# RFM69_USB_Gateway_0_93.net
KiCad netlist of a schematic drawn in EAGLE
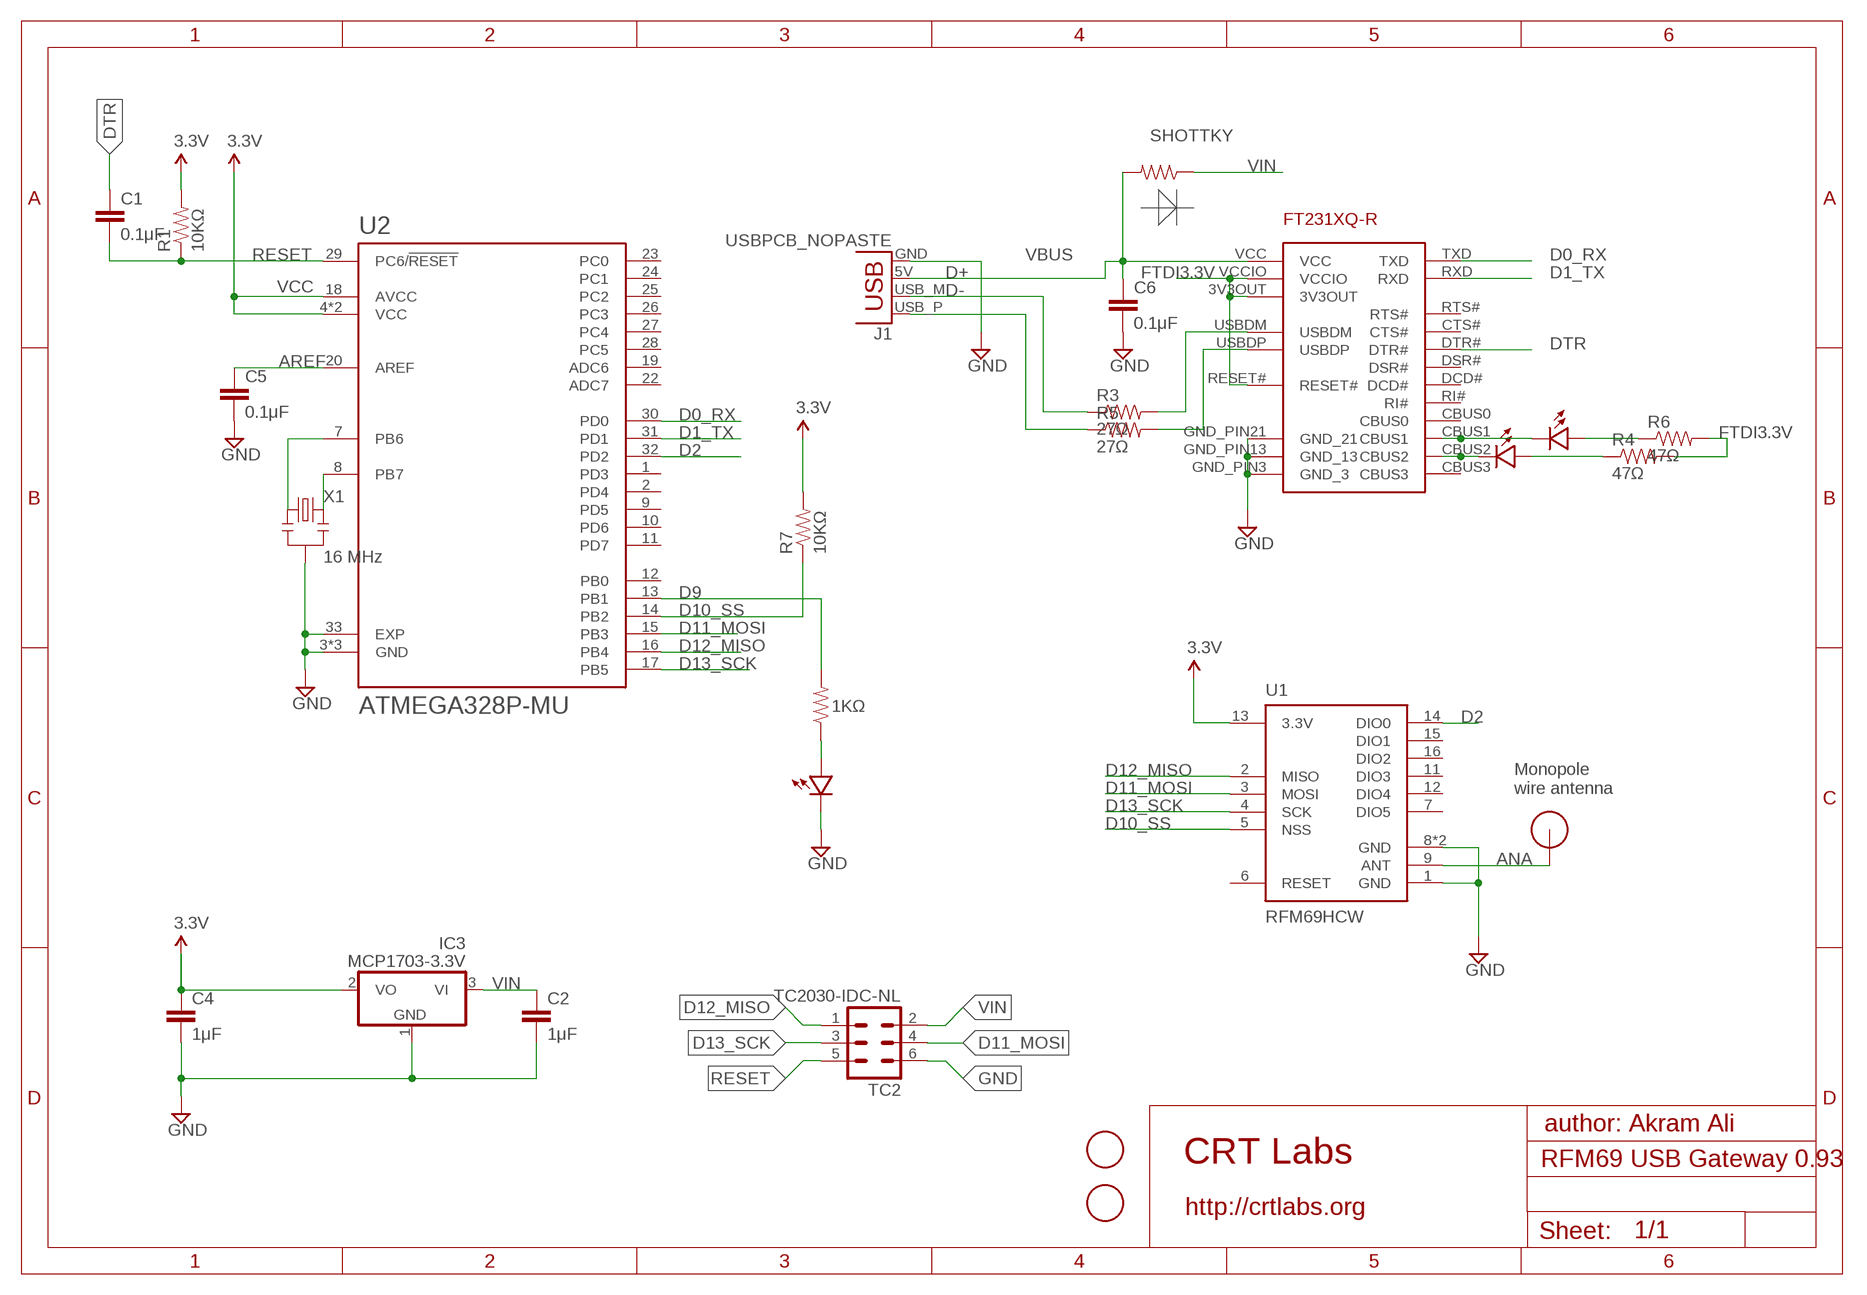
[diagram p0: schematic, sheet 1]

(export (version "E")
  (design (tool "Eeschema 10.0.6"))
  (components
    (comp (ref "C1")
      (value "0.1μF")
      (footprint "eagle-import:0805")
      (fields (field (name "MPN") "CC0805KRX7R9BB104"))
      (libsource (lib "eagle-import") (part "SparkFun_CAP0805"))
    )
    (comp (ref "C2")
      (value "1μF")
      (footprint "eagle-import:0805")
      (fields (field (name "MPN") "CC0805ZRY5V8BB105"))
      (libsource (lib "eagle-import") (part "SparkFun_CAP0805"))
    )
    (comp (ref "C4")
      (value "1μF")
      (footprint "eagle-import:0805")
      (fields (field (name "MPN") "CC0805ZRY5V8BB105"))
      (libsource (lib "eagle-import") (part "CAP0805"))
    )
    (comp (ref "C5")
      (value "0.1μF")
      (footprint "eagle-import:0805")
      (fields (field (name "MPN") "CC0805KRX7R9BB104"))
      (libsource (lib "eagle-import") (part "SparkFun_CAP0805"))
    )
    (comp (ref "C6")
      (value "0.1μF")
      (footprint "eagle-import:0805")
      (fields (field (name "MPN") "CC0805KRX7R9BB104"))
      (libsource (lib "eagle-import") (part "SparkFun_CAP0805"))
    )
    (comp (ref "D")
      (value "SHOTTKY")
      (footprint "eagle-import:0805")
      (fields (field (name "MPN") "SD0805S040S0R5"))
      (libsource (lib "eagle-import") (part "RESISTOR0805"))
    )
    (comp (ref "FT231XQ-R")
      (value "FT231XQ-R")
      (footprint "eagle-import:FTDI_FT231XQ-R_PACKAGE")
      (libsource (lib "eagle-import") (part "FT231XQ-R"))
    )
    (comp (ref "IC3")
      (value "MCP1703-3.3V")
      (footprint "eagle-import:SOT23")
      (fields (field (name "MPN") "MCP1703T-2502E/CB"))
      (libsource (lib "eagle-import") (part "MCP1703CB"))
    )
    (comp (ref "J1")
      (value "USBPCB_NOPASTE")
      (footprint "eagle-import:USB-A-PCB-NOPASTE")
      (libsource (lib "eagle-import") (part "USBPCB_NOPASTE"))
    )
    (comp (ref "R1")
      (value "10KΩ")
      (footprint "eagle-import:0805")
      (fields (field (name "MPN") "RC0805FR-0710KL"))
      (libsource (lib "eagle-import") (part "RESISTOR0805"))
    )
    (comp (ref "R2")
      (value "1KΩ")
      (footprint "eagle-import:0805")
      (fields (field (name "MPN") "RC0805FR-071KL"))
      (libsource (lib "eagle-import") (part "SparkFun_RESISTOR0805-RES"))
    )
    (comp (ref "R3")
      (value "27Ω")
      (footprint "eagle-import:0805")
      (fields (field (name "MPN") "RC0805FR-0727RL"))
      (libsource (lib "eagle-import") (part "SparkFun_RESISTOR0805-RES"))
    )
    (comp (ref "R4")
      (value "47Ω")
      (footprint "eagle-import:0805")
      (fields (field (name "MPN") "RC0805FR-0747RL "))
      (libsource (lib "eagle-import") (part "SparkFun_RESISTOR0805-RES"))
    )
    (comp (ref "R5")
      (value "27Ω")
      (footprint "eagle-import:0805")
      (fields (field (name "MPN") "RC0805FR-0727RL"))
      (libsource (lib "eagle-import") (part "SparkFun_RESISTOR0805-RES"))
    )
    (comp (ref "R6")
      (value "47Ω")
      (footprint "eagle-import:0805")
      (fields (field (name "MPN") "RC0805FR-0747RL "))
      (libsource (lib "eagle-import") (part "SparkFun_RESISTOR0805-RES"))
    )
    (comp (ref "R7")
      (value "10KΩ")
      (footprint "eagle-import:0805")
      (fields (field (name "MPN") "RC0805FR-0710KL"))
      (libsource (lib "eagle-import") (part "SparkFun_RESISTOR0805-RES"))
    )
    (comp (ref "RX")
      (value "Green")
      (footprint "eagle-import:0805-LED")
      (fields (field (name "MPN") "LG R971-KN-1"))
      (libsource (lib "eagle-import") (part "LED0805"))
    )
    (comp (ref "TC2")
      (value "TC2030-IDC-NL")
      (footprint "eagle-import:TC2030-IDC-NL")
      (libsource (lib "eagle-import") (part "TC2030-IDC-NL"))
    )
    (comp (ref "TX")
      (value "Red")
      (footprint "eagle-import:0805-LED")
      (fields (field (name "MPN") "LG R971-KN-1"))
      (libsource (lib "eagle-import") (part "LED0805"))
    )
    (comp (ref "U$2")
      (value "Status")
      (footprint "eagle-import:0805-LED")
      (fields (field (name "MPN") "LG R971-KN-1"))
      (libsource (lib "eagle-import") (part "LED0805"))
    )
    (comp (ref "U$3")
      (value "FIDUCIAL")
      (footprint "eagle-import:FIDUCIAL_1MM")
      (libsource (lib "eagle-import") (part "FIDUCIAL"))
    )
    (comp (ref "U$4")
      (value "FIDUCIAL")
      (footprint "eagle-import:FIDUCIAL_1MM")
      (libsource (lib "eagle-import") (part "FIDUCIAL"))
    )
    (comp (ref "U$6")
      (value "RFM12B_ANTENNA")
      (footprint "eagle-import:RFM12B-ANTENNA")
      (libsource (lib "eagle-import") (part "RFM12B_ANTENNA"))
    )
    (comp (ref "U1")
      (value "RFM69HCW")
      (footprint "eagle-import:RFM69HCW-XXXS2")
      (fields (field (name "MPN") "RFM69HW"))
      (libsource (lib "eagle-import") (part "RFM69HCW"))
    )
    (comp (ref "U2")
      (value "ATMEGA328P-MU")
      (footprint "eagle-import:QFN50P500X500X100-33N")
      (fields (field (name "MF") "Atmel") (field (name "MPN") "ATmega328P-MU"))
      (libsource (lib "eagle-import") (part "ATMEGA328P-MU"))
    )
    (comp (ref "X1")
      (value "16 MHz")
      (footprint "eagle-import:RESONATOR-SMD")
      (fields (field (name "MPN") "CSTCE16M0V53-R0"))
      (libsource (lib "eagle-import") (part "RESONATORSMD"))
    )
  )
  (nets
    (net (code "1") (name "/ANA") (class "Default")
      (node (ref "U$6") (pin "P$1") (pinfunction "1_P$1") (pintype "bidirectional"))
      (node (ref "U1") (pin "9") (pinfunction "ANT_9") (pintype "passive"))
    )
    (net (code "2") (name "/AREF") (class "Default")
      (node (ref "C5") (pin "1") (pinfunction "1_1") (pintype "passive"))
      (node (ref "U2") (pin "20") (pinfunction "AREF_20") (pintype "input"))
    )
    (net (code "3") (name "/D+") (class "Default")
      (node (ref "J1") (pin "USB_P") (pinfunction "D+_USB_P") (pintype "bidirectional"))
      (node (ref "R5") (pin "1") (pinfunction "1_1") (pintype "passive"))
    )
    (net (code "4") (name "/D-") (class "Default")
      (node (ref "J1") (pin "USB_M") (pinfunction "D-_USB_M") (pintype "bidirectional"))
      (node (ref "R3") (pin "1") (pinfunction "1_1") (pintype "passive"))
    )
    (net (code "5") (name "/D0_RX") (class "Default")
      (node (ref "FT231XQ-R") (pin "TXD") (pinfunction "TXD_TXD") (pintype "bidirectional"))
      (node (ref "U2") (pin "30") (pinfunction "PD0_30") (pintype "bidirectional"))
    )
    (net (code "6") (name "/D1_TX") (class "Default")
      (node (ref "FT231XQ-R") (pin "RXD") (pinfunction "RXD_RXD") (pintype "bidirectional"))
      (node (ref "U2") (pin "31") (pinfunction "PD1_31") (pintype "bidirectional"))
    )
    (net (code "7") (name "/D2") (class "Default")
      (node (ref "U1") (pin "14") (pinfunction "DIO0_14") (pintype "bidirectional"))
      (node (ref "U2") (pin "32") (pinfunction "PD2_32") (pintype "bidirectional"))
    )
    (net (code "8") (name "/D9") (class "Default")
      (node (ref "R2") (pin "2") (pinfunction "2_2") (pintype "passive"))
      (node (ref "U2") (pin "13") (pinfunction "PB1_13") (pintype "bidirectional"))
    )
    (net (code "9") (name "/D10_SS") (class "Default")
      (node (ref "R7") (pin "1") (pinfunction "1_1") (pintype "passive"))
      (node (ref "U1") (pin "5") (pinfunction "NSS_5") (pintype "input"))
      (node (ref "U2") (pin "14") (pinfunction "PB2_14") (pintype "bidirectional"))
    )
    (net (code "10") (name "/FTDI3.3V") (class "Default")
      (node (ref "FT231XQ-R") (pin "3V3OUT") (pinfunction "3V3OUT_3V3OUT") (pintype "bidirectional"))
      (node (ref "FT231XQ-R") (pin "RESET#") (pinfunction "RESET#_RESET#") (pintype "bidirectional"))
      (node (ref "FT231XQ-R") (pin "VCCIO") (pinfunction "VCCIO_VCCIO") (pintype "bidirectional"))
      (node (ref "R4") (pin "2") (pinfunction "2_2") (pintype "passive"))
      (node (ref "R6") (pin "2") (pinfunction "2_2") (pintype "passive"))
    )
    (net (code "11") (name "/VBUS") (class "Default")
      (node (ref "C6") (pin "1") (pinfunction "1_1") (pintype "passive"))
      (node (ref "D") (pin "2") (pinfunction "2_2") (pintype "passive"))
      (node (ref "FT231XQ-R") (pin "VCC") (pinfunction "VCC_VCC") (pintype "bidirectional"))
      (node (ref "J1") (pin "5V") (pinfunction "VBUS_5V") (pintype "bidirectional"))
    )
    (net (code "12") (name "3.3V") (class "Default")
      (node (ref "C4") (pin "1") (pinfunction "1_1") (pintype "passive"))
      (node (ref "IC3") (pin "2") (pinfunction "VO_2") (pintype "passive"))
      (node (ref "R1") (pin "2") (pinfunction "2_2") (pintype "passive"))
      (node (ref "R7") (pin "2") (pinfunction "2_2") (pintype "passive"))
      (node (ref "U1") (pin "13") (pinfunction "3.3V_13") (pintype "power_in"))
      (node (ref "U2") (pin "18") (pinfunction "AVCC_18") (pintype "power_in"))
      (node (ref "U2") (pin "4") (pinfunction "VCC_4") (pintype "power_in"))
      (node (ref "U2") (pin "6") (pinfunction "VCC_6") (pintype "power_in"))
    )
    (net (code "13") (name "D11_MOSI") (class "Default")
      (node (ref "TC2") (pin "4") (pinfunction "4_4") (pintype "passive"))
      (node (ref "U1") (pin "3") (pinfunction "MOSI_3") (pintype "input"))
      (node (ref "U2") (pin "15") (pinfunction "PB3_15") (pintype "bidirectional"))
    )
    (net (code "14") (name "D12_MISO") (class "Default")
      (node (ref "TC2") (pin "1") (pinfunction "1_1") (pintype "passive"))
      (node (ref "U1") (pin "2") (pinfunction "MISO_2") (pintype "bidirectional"))
      (node (ref "U2") (pin "16") (pinfunction "PB4_16") (pintype "bidirectional"))
    )
    (net (code "15") (name "D13_SCK") (class "Default")
      (node (ref "TC2") (pin "3") (pinfunction "3_3") (pintype "passive"))
      (node (ref "U1") (pin "4") (pinfunction "SCK_4") (pintype "input"))
      (node (ref "U2") (pin "17") (pinfunction "PB5_17") (pintype "bidirectional"))
    )
    (net (code "16") (name "DTR") (class "Default")
      (node (ref "C1") (pin "1") (pinfunction "1_1") (pintype "passive"))
      (node (ref "FT231XQ-R") (pin "DTR#") (pinfunction "DTR#_DTR#") (pintype "bidirectional"))
    )
    (net (code "17") (name "GND") (class "Default")
      (node (ref "C2") (pin "2") (pinfunction "2_2") (pintype "passive"))
      (node (ref "C4") (pin "2") (pinfunction "2_2") (pintype "passive"))
      (node (ref "C5") (pin "2") (pinfunction "2_2") (pintype "passive"))
      (node (ref "C6") (pin "2") (pinfunction "2_2") (pintype "passive"))
      (node (ref "FT231XQ-R") (pin "GND_PIN13") (pinfunction "GND_13_GND_PIN13") (pintype "bidirectional"))
      (node (ref "FT231XQ-R") (pin "GND_PIN21") (pinfunction "GND_21_GND_PIN21") (pintype "bidirectional"))
      (node (ref "FT231XQ-R") (pin "GND_PIN3") (pinfunction "GND_3_GND_PIN3") (pintype "bidirectional"))
      (node (ref "IC3") (pin "1") (pinfunction "GND_1") (pintype "passive"))
      (node (ref "J1") (pin "GND") (pinfunction "GND_GND") (pintype "bidirectional"))
      (node (ref "TC2") (pin "6") (pinfunction "6_6") (pintype "passive"))
      (node (ref "U$2") (pin "MINUS") (pinfunction "MINUS_MINUS") (pintype "passive"))
      (node (ref "U1") (pin "1") (pinfunction "GND_1") (pintype "power_in"))
      (node (ref "U1") (pin "10") (pinfunction "GND_10") (pintype "power_in"))
      (node (ref "U1") (pin "8") (pinfunction "GND_8") (pintype "power_in"))
      (node (ref "U2") (pin "21") (pinfunction "GND_21") (pintype "power_in"))
      (node (ref "U2") (pin "3") (pinfunction "GND_3") (pintype "power_in"))
      (node (ref "U2") (pin "33") (pinfunction "EXP_33") (pintype "power_in"))
      (node (ref "U2") (pin "5") (pinfunction "GND_5") (pintype "power_in"))
      (node (ref "X1") (pin "2") (pinfunction "2_2") (pintype "passive"))
    )
    (net (code "18") (name "Net-(FT231XQ-R-PadCBUS1)") (class "Default")
      (node (ref "FT231XQ-R") (pin "CBUS1") (pinfunction "CBUS1_CBUS1") (pintype "bidirectional"))
      (node (ref "RX") (pin "MINUS") (pinfunction "MINUS_MINUS") (pintype "passive"))
    )
    (net (code "19") (name "Net-(FT231XQ-R-PadCBUS2)") (class "Default")
      (node (ref "FT231XQ-R") (pin "CBUS2") (pinfunction "CBUS2_CBUS2") (pintype "bidirectional"))
      (node (ref "TX") (pin "MINUS") (pinfunction "MINUS_MINUS") (pintype "passive"))
    )
    (net (code "20") (name "Net-(FT231XQ-R-PadUSBDM)") (class "Default")
      (node (ref "FT231XQ-R") (pin "USBDM") (pinfunction "USBDM_USBDM") (pintype "bidirectional"))
      (node (ref "R3") (pin "2") (pinfunction "2_2") (pintype "passive"))
    )
    (net (code "21") (name "Net-(FT231XQ-R-PadUSBDP)") (class "Default")
      (node (ref "FT231XQ-R") (pin "USBDP") (pinfunction "USBDP_USBDP") (pintype "bidirectional"))
      (node (ref "R5") (pin "2") (pinfunction "2_2") (pintype "passive"))
    )
    (net (code "22") (name "Net-(R2-Pad1)") (class "Default")
      (node (ref "R2") (pin "1") (pinfunction "1_1") (pintype "passive"))
      (node (ref "U$2") (pin "PLUS") (pinfunction "PLUS_PLUS") (pintype "passive"))
    )
    (net (code "23") (name "Net-(R4-Pad1)") (class "Default")
      (node (ref "R4") (pin "1") (pinfunction "1_1") (pintype "passive"))
      (node (ref "TX") (pin "PLUS") (pinfunction "PLUS_PLUS") (pintype "passive"))
    )
    (net (code "24") (name "Net-(R6-Pad1)") (class "Default")
      (node (ref "R6") (pin "1") (pinfunction "1_1") (pintype "passive"))
      (node (ref "RX") (pin "PLUS") (pinfunction "PLUS_PLUS") (pintype "passive"))
    )
    (net (code "25") (name "Net-(U2-PB6)") (class "Default")
      (node (ref "U2") (pin "7") (pinfunction "PB6_7") (pintype "bidirectional"))
      (node (ref "X1") (pin "1") (pinfunction "1_1") (pintype "passive"))
    )
    (net (code "26") (name "Net-(U2-PB7)") (class "Default")
      (node (ref "U2") (pin "8") (pinfunction "PB7_8") (pintype "bidirectional"))
      (node (ref "X1") (pin "3") (pinfunction "3_3") (pintype "passive"))
    )
    (net (code "27") (name "RESET") (class "Default")
      (node (ref "C1") (pin "2") (pinfunction "2_2") (pintype "passive"))
      (node (ref "R1") (pin "1") (pinfunction "1_1") (pintype "passive"))
      (node (ref "TC2") (pin "5") (pinfunction "5_5") (pintype "passive"))
      (node (ref "U2") (pin "29") (pinfunction "PC6/~{RESET}_29") (pintype "bidirectional"))
    )
    (net (code "28") (name "VIN") (class "Default")
      (node (ref "C2") (pin "1") (pinfunction "1_1") (pintype "passive"))
      (node (ref "D") (pin "1") (pinfunction "1_1") (pintype "passive"))
      (node (ref "IC3") (pin "3") (pinfunction "VI_3") (pintype "input"))
      (node (ref "TC2") (pin "2") (pinfunction "2_2") (pintype "passive"))
    )
    (net (code "29") (name "unconnected-(FT231XQ-R-PadCBUS0)") (class "Default")
      (node (ref "FT231XQ-R") (pin "CBUS0") (pinfunction "CBUS0_CBUS0") (pintype "bidirectional"))
    )
    (net (code "30") (name "unconnected-(FT231XQ-R-PadCBUS3)") (class "Default")
      (node (ref "FT231XQ-R") (pin "CBUS3") (pinfunction "CBUS3_CBUS3") (pintype "bidirectional"))
    )
    (net (code "31") (name "unconnected-(FT231XQ-R-PadCTS#)") (class "Default")
      (node (ref "FT231XQ-R") (pin "CTS#") (pinfunction "CTS#_CTS#") (pintype "bidirectional"))
    )
    (net (code "32") (name "unconnected-(FT231XQ-R-PadDCD#)") (class "Default")
      (node (ref "FT231XQ-R") (pin "DCD#") (pinfunction "DCD#_DCD#") (pintype "bidirectional"))
    )
    (net (code "33") (name "unconnected-(FT231XQ-R-PadDSR#)") (class "Default")
      (node (ref "FT231XQ-R") (pin "DSR#") (pinfunction "DSR#_DSR#") (pintype "bidirectional"))
    )
    (net (code "34") (name "unconnected-(FT231XQ-R-PadRI#)") (class "Default")
      (node (ref "FT231XQ-R") (pin "RI#") (pinfunction "RI#_RI#") (pintype "bidirectional"))
    )
    (net (code "35") (name "unconnected-(FT231XQ-R-PadRTS#)") (class "Default")
      (node (ref "FT231XQ-R") (pin "RTS#") (pinfunction "RTS#_RTS#") (pintype "bidirectional"))
    )
    (net (code "36") (name "unconnected-(U1-DIO1-Pad15)") (class "Default")
      (node (ref "U1") (pin "15") (pinfunction "DIO1_15") (pintype "bidirectional"))
    )
    (net (code "37") (name "unconnected-(U1-DIO2-Pad16)") (class "Default")
      (node (ref "U1") (pin "16") (pinfunction "DIO2_16") (pintype "bidirectional"))
    )
    (net (code "38") (name "unconnected-(U1-DIO3-Pad11)") (class "Default")
      (node (ref "U1") (pin "11") (pinfunction "DIO3_11") (pintype "bidirectional"))
    )
    (net (code "39") (name "unconnected-(U1-DIO4-Pad12)") (class "Default")
      (node (ref "U1") (pin "12") (pinfunction "DIO4_12") (pintype "bidirectional"))
    )
    (net (code "40") (name "unconnected-(U1-DIO5-Pad7)") (class "Default")
      (node (ref "U1") (pin "7") (pinfunction "DIO5_7") (pintype "bidirectional"))
    )
    (net (code "41") (name "unconnected-(U1-RESET-Pad6)") (class "Default")
      (node (ref "U1") (pin "6") (pinfunction "RESET_6") (pintype "input"))
    )
    (net (code "42") (name "unconnected-(U2-ADC6-Pad19)") (class "Default")
      (node (ref "U2") (pin "19") (pinfunction "ADC6_19") (pintype "bidirectional"))
    )
    (net (code "43") (name "unconnected-(U2-ADC7-Pad22)") (class "Default")
      (node (ref "U2") (pin "22") (pinfunction "ADC7_22") (pintype "bidirectional"))
    )
    (net (code "44") (name "unconnected-(U2-PB0-Pad12)") (class "Default")
      (node (ref "U2") (pin "12") (pinfunction "PB0_12") (pintype "bidirectional"))
    )
    (net (code "45") (name "unconnected-(U2-PC0-Pad23)") (class "Default")
      (node (ref "U2") (pin "23") (pinfunction "PC0_23") (pintype "bidirectional"))
    )
    (net (code "46") (name "unconnected-(U2-PC1-Pad24)") (class "Default")
      (node (ref "U2") (pin "24") (pinfunction "PC1_24") (pintype "bidirectional"))
    )
    (net (code "47") (name "unconnected-(U2-PC2-Pad25)") (class "Default")
      (node (ref "U2") (pin "25") (pinfunction "PC2_25") (pintype "bidirectional"))
    )
    (net (code "48") (name "unconnected-(U2-PC3-Pad26)") (class "Default")
      (node (ref "U2") (pin "26") (pinfunction "PC3_26") (pintype "bidirectional"))
    )
    (net (code "49") (name "unconnected-(U2-PC4-Pad27)") (class "Default")
      (node (ref "U2") (pin "27") (pinfunction "PC4_27") (pintype "bidirectional"))
    )
    (net (code "50") (name "unconnected-(U2-PC5-Pad28)") (class "Default")
      (node (ref "U2") (pin "28") (pinfunction "PC5_28") (pintype "bidirectional"))
    )
    (net (code "51") (name "unconnected-(U2-PD3-Pad1)") (class "Default")
      (node (ref "U2") (pin "1") (pinfunction "PD3_1") (pintype "bidirectional"))
    )
    (net (code "52") (name "unconnected-(U2-PD4-Pad2)") (class "Default")
      (node (ref "U2") (pin "2") (pinfunction "PD4_2") (pintype "bidirectional"))
    )
    (net (code "53") (name "unconnected-(U2-PD5-Pad9)") (class "Default")
      (node (ref "U2") (pin "9") (pinfunction "PD5_9") (pintype "bidirectional"))
    )
    (net (code "54") (name "unconnected-(U2-PD6-Pad10)") (class "Default")
      (node (ref "U2") (pin "10") (pinfunction "PD6_10") (pintype "bidirectional"))
    )
    (net (code "55") (name "unconnected-(U2-PD7-Pad11)") (class "Default")
      (node (ref "U2") (pin "11") (pinfunction "PD7_11") (pintype "bidirectional"))
    )
  )
)
